# Antenna_Supervisor.net
KiCad netlist of a schematic drawn in Altium Designer
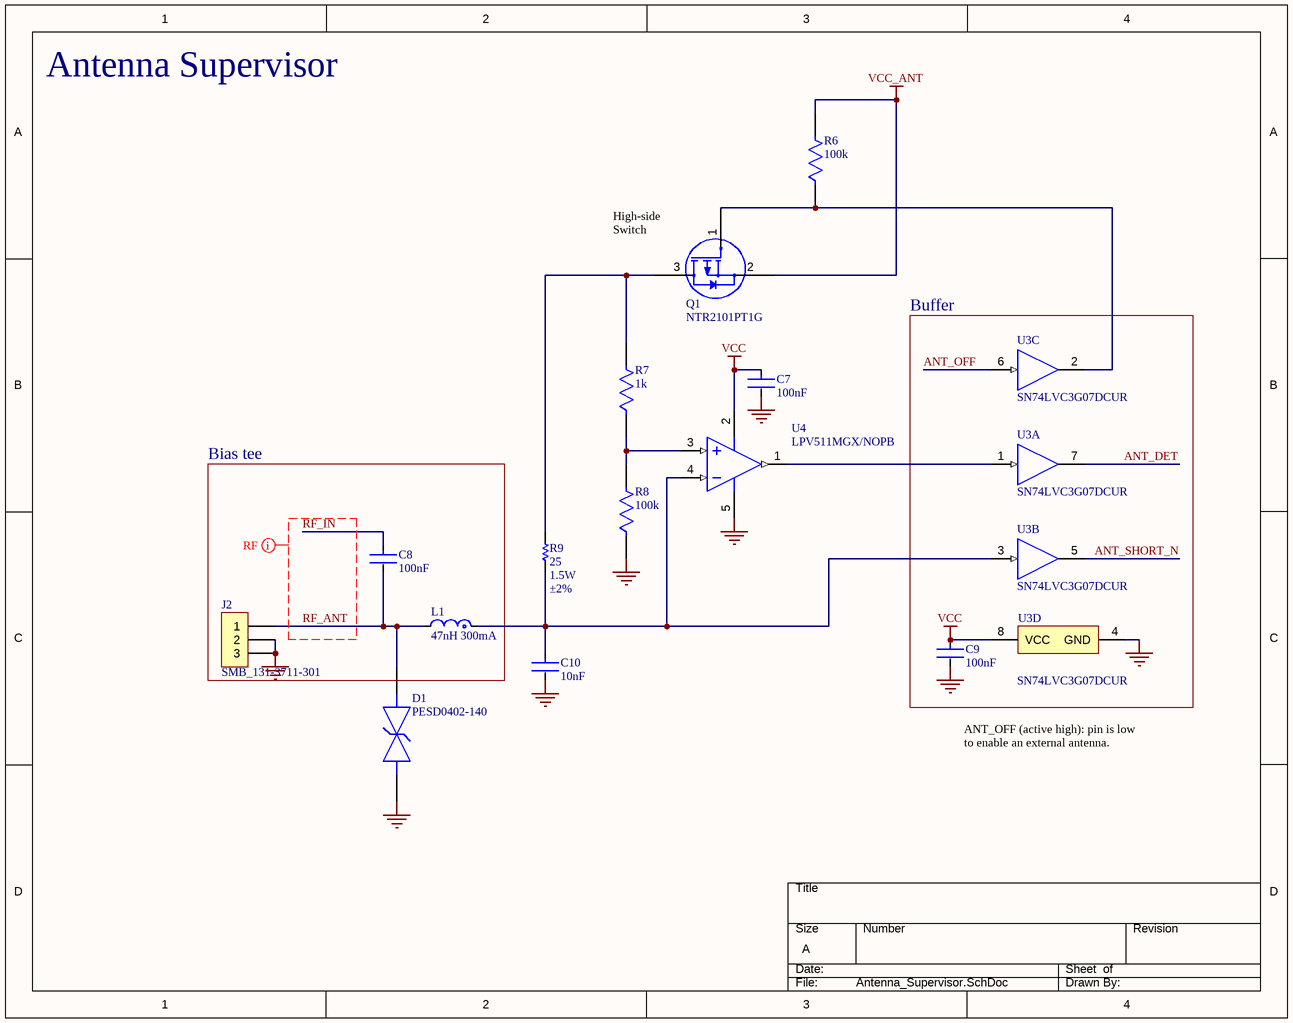
[diagram p0: Antenna_Supervisor.SchDoc]

(export (version "E")
  (design (tool "Eeschema 10.0.6"))
  (components
    (comp (ref "C7")
      (value "100nF")
      (footprint "FP-0402-L_1_0_0_05-W_0_5-IPC_B")
      (description "None")
      (fields (field (name "TOLERANCE") "10%"))
      (libsource (lib "Altium Content Vault") (part "b4654b650e69147ec39a6b967a45e02"))
    )
    (comp (ref "C8")
      (value "100nF")
      (footprint "FP-0402-L_1_0_0_05-W_0_5-IPC_B")
      (description "None")
      (fields (field (name "TOLERANCE") "10%"))
      (libsource (lib "Altium Content Vault") (part "b4654b650e69147ec39a6b967a45e02"))
    )
    (comp (ref "C9")
      (value "100nF")
      (footprint "FP-0402-L_1_0_0_05-W_0_5-IPC_B")
      (description "None")
      (fields (field (name "TOLERANCE") "10%"))
      (libsource (lib "Altium Content Vault") (part "b4654b650e69147ec39a6b967a45e02"))
    )
    (comp (ref "C10")
      (value "10nF")
      (footprint "FP-GRM033-0_03-IPC_B")
      (description "Chip Multilayer Ceramic Capacitors for General Purpose, 0201, 10000pF, X7R, 15%, 10%, 16V")
      (fields (field (name "TOLERANCE") "10%"))
      (libsource (lib "Altium Content Vault") (part "b4654b650e69147ec39a6b967a45e02"))
    )
    (comp (ref "D1")
      (value "PESD0402-140")
      (footprint "FP-PESD0402-MFG")
      (description "TVS DIODE 14V 40V 0402")
      (fields
        (field (name "OCTOPART") "https://octopart.com/pesd0402-140-littelfuse-74215061")
        (field (name "MANUFACTURER") "Littelfuse Inc.")
      )
      (libsource (lib "Altium Content Vault") (part "edccc070dd5cba1f9372128faf3915e"))
    )
    (comp (ref "J2")
      (value "SMB_131-3711-301")
      (footprint "CONN_131-3711-301")
      (description "Rf Coaxial Board Mount Connector")
      (fields
        (field (name "MANUFACTURER") "Bel Cinch")
        (field (name "MANUFACTURER PART NUMBER") "131-3711-301")
      )
      (libsource (lib "MyLibrary") (part "CONN_131-3711-301"))
    )
    (comp (ref "L1")
      (value "47nH 300mA")
      (footprint "FP-LQG15HH_02-IPC_B")
      (description "Multilayer type RF Inductor 47nH ±5% 0.72Ω 300mA 0402")
      (fields (field (name "TOLERANCE") "5%"))
      (libsource (lib "Altium Content Vault") (part "4cc4b267dca4c8e51f7102f422741d8"))
    )
    (comp (ref "Q1")
      (value "onsemi_NTR2101PT1G")
      (footprint "SOT23_3pins_300x140x112")
      (description "MOSFET, P-CH, 8VDS, 3.7A ID, 0.052 OHM RDS(ON)@4.5VGS/3.5A, SOT-23-3")
      (fields
        (field (name "MANUFACTURER") "onsemi")
        (field (name "MANUFACTURER PART NUMBER") "NTR2101PT1G")
        (field (name "INTERNAL PART NUMBER") "839-00735-00")
      )
      (libsource (lib "RL Research Altium Server") (part "Transistor_MOS-P-CH_3pins_1G_1S_1D_DIO"))
    )
    (comp (ref "R6")
      (value "100k")
      (footprint "FP-RMCF0402-IPC_C")
      (description "100kΩ ±1% 0.063W 0402 Thick Film Chip Resistor AEC-Q200 compliant")
      (fields (field (name "TOLERANCE") "1%"))
      (libsource (lib "Altium Content Vault") (part "1029c3af85768c4190bb7ad29bc67b5"))
    )
    (comp (ref "R7")
      (value "1k")
      (footprint "FP-RMCF0402-MFG")
      (description "1kΩ ±1% 0.063W 0402 Thick Film Chip Resistor AEC-Q200 compliant")
      (fields (field (name "TOLERANCE") "1%"))
      (libsource (lib "Altium Content Vault") (part "1029c3af85768c4190bb7ad29bc67b5"))
    )
    (comp (ref "R8")
      (value "100k")
      (footprint "FP-RMCF0402-IPC_C")
      (description "100kΩ ±1% 0.063W 0402 Thick Film Chip Resistor AEC-Q200 compliant")
      (fields (field (name "TOLERANCE") "1%"))
      (libsource (lib "Altium Content Vault") (part "1029c3af85768c4190bb7ad29bc67b5"))
    )
    (comp (ref "R9")
      (value "Vishay_RCP0603W25R0GEB")
      (footprint "RESC1608X055N")
      (description "RES, 25 OHM, 2%, 1.5W, 150PPM/C, 0603")
      (fields
        (field (name "RESISTANCE") "25")
        (field (name "POWER (WATTS)") "1.5W")
        (field (name "TOLERANCE") "±2%")
        (field (name "INTERNAL PART NUMBER") "822-00198-00")
        (field (name "MANUFACTURER") "Vishay")
      )
      (libsource (lib "RL Research Altium Server") (part "Resistor_300mil"))
    )
    (comp (ref "U3")
      (value "SN74LVC3G07DCUR")
      (footprint "DCU0008A_N")
      (description "Triple Buffer/Driver With Open-Drain Output, DCU0008A, LARGE T&R")
      (fields
        (field (name "GENERIC PART NUMBER") "SN74LVC3G07")
        (field (name "MANUFACTURER") "Texas Instruments")
      )
      (libsource (lib "Altium Content Vault") (part "TI-SN74XXX3G0X-XX-8"))
    )
    (comp (ref "U4")
      (value "LPV511MGX/NOPB")
      (footprint "DCK0005A_N")
      (description "micropower Rail-to-Rail Input and Output Operational Amplifier, 5-pin SC-70, Pb-Free")
      (fields (field (name "MANUFACTURER") "Texas Instruments"))
      (libsource (lib "Altium Content Vault") (part "AMP-OPA-LM7121-5"))
    )
  )
  (nets
    (net (code "1") (name "/ANT_DET") (class "Default")
      (node (ref "U3") (pin "7") (pinfunction "1Y_7") (pintype "open_collector"))
    )
    (net (code "2") (name "/ANT_OFF") (class "Default")
      (node (ref "U3") (pin "6") (pinfunction "3A_6") (pintype "input"))
    )
    (net (code "3") (name "/ANT_SHORT_N") (class "Default")
      (node (ref "U3") (pin "5") (pinfunction "2Y_5") (pintype "open_collector"))
    )
    (net (code "4") (name "/RF_ANT") (class "Default")
      (node (ref "C8") (pin "2") (pinfunction "2_2") (pintype "passive"))
      (node (ref "D1") (pin "2") (pinfunction "2_2") (pintype "passive"))
      (node (ref "J2") (pin "1") (pinfunction "1_1") (pintype "passive"))
      (node (ref "L1") (pin "2") (pinfunction "2_2") (pintype "passive"))
    )
    (net (code "5") (name "/RF_IN") (class "Default")
      (node (ref "C8") (pin "1") (pinfunction "1_1") (pintype "passive"))
    )
    (net (code "6") (name "GND") (class "Default")
      (node (ref "C10") (pin "2") (pinfunction "2_2") (pintype "passive"))
      (node (ref "C7") (pin "2") (pinfunction "2_2") (pintype "passive"))
      (node (ref "C9") (pin "2") (pinfunction "2_2") (pintype "passive"))
      (node (ref "D1") (pin "1") (pinfunction "1_1") (pintype "passive"))
      (node (ref "J2") (pin "2") (pinfunction "2_2") (pintype "passive"))
      (node (ref "J2") (pin "3") (pinfunction "3_3") (pintype "passive"))
      (node (ref "R8") (pin "1") (pinfunction "1_1") (pintype "passive"))
      (node (ref "U3") (pin "4") (pinfunction "GND_4") (pintype "power_in"))
      (node (ref "U4") (pin "5") (pinfunction "V+_5") (pintype "power_in"))
    )
    (net (code "7") (name "Net-(Q1-D)") (class "Default")
      (node (ref "Q1") (pin "3") (pinfunction "D_3") (pintype "passive"))
      (node (ref "R7") (pin "2") (pinfunction "2_2") (pintype "passive"))
      (node (ref "R9") (pin "1") (pinfunction "1_1") (pintype "passive"))
    )
    (net (code "8") (name "Net-(Q1-G)") (class "Default")
      (node (ref "Q1") (pin "1") (pinfunction "G_1") (pintype "passive"))
      (node (ref "R6") (pin "1") (pinfunction "1_1") (pintype "passive"))
      (node (ref "U3") (pin "2") (pinfunction "3Y_2") (pintype "open_collector"))
    )
    (net (code "9") (name "Net-(U3A-1A)") (class "Default")
      (node (ref "U3") (pin "1") (pinfunction "1A_1") (pintype "input"))
      (node (ref "U4") (pin "1") (pinfunction "OUT_1") (pintype "output"))
    )
    (net (code "10") (name "Net-(U3B-2A)") (class "Default")
      (node (ref "C10") (pin "1") (pinfunction "1_1") (pintype "passive"))
      (node (ref "L1") (pin "1") (pinfunction "1_1") (pintype "passive"))
      (node (ref "R9") (pin "2") (pinfunction "2_2") (pintype "passive"))
      (node (ref "U3") (pin "3") (pinfunction "2A_3") (pintype "input"))
      (node (ref "U4") (pin "4") (pinfunction "IN-_4") (pintype "input"))
    )
    (net (code "11") (name "Net-(U4-IN+)") (class "Default")
      (node (ref "R7") (pin "1") (pinfunction "1_1") (pintype "passive"))
      (node (ref "R8") (pin "2") (pinfunction "2_2") (pintype "passive"))
      (node (ref "U4") (pin "3") (pinfunction "IN+_3") (pintype "input"))
    )
    (net (code "12") (name "VCC") (class "Default")
      (node (ref "C7") (pin "1") (pinfunction "1_1") (pintype "passive"))
      (node (ref "C9") (pin "1") (pinfunction "1_1") (pintype "passive"))
      (node (ref "U3") (pin "8") (pinfunction "VCC_8") (pintype "power_in"))
      (node (ref "U4") (pin "2") (pinfunction "V-_2") (pintype "power_in"))
    )
    (net (code "13") (name "VCC_ANT") (class "Default")
      (node (ref "Q1") (pin "2") (pinfunction "S_2") (pintype "passive"))
      (node (ref "R6") (pin "2") (pinfunction "2_2") (pintype "passive"))
    )
  )
)
